# Sheet1.net
KiCad netlist of a schematic drawn in Altium Designer
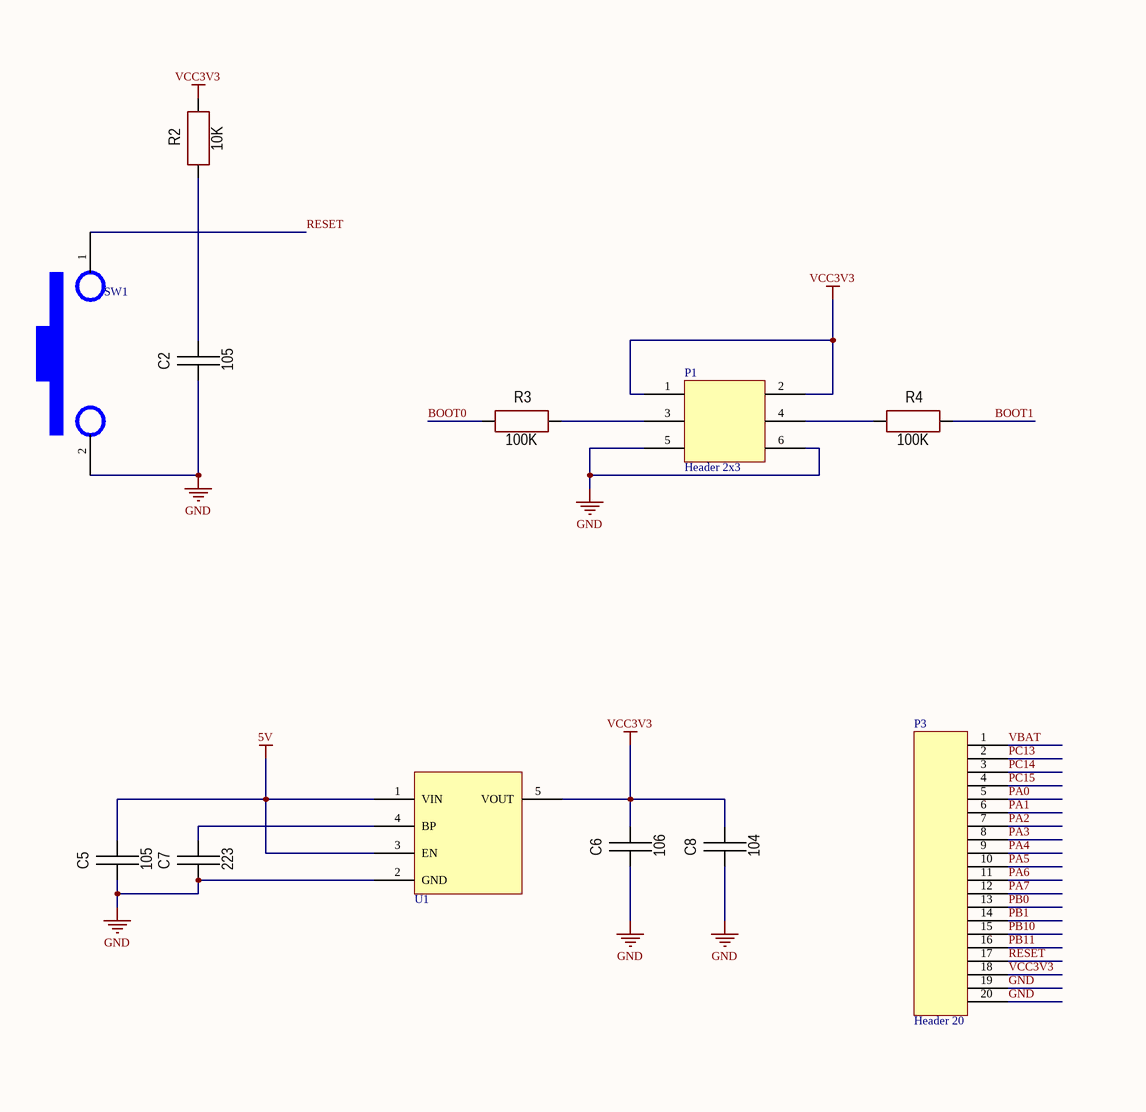
[diagram p0: Sheet1.SchDoc, top left]
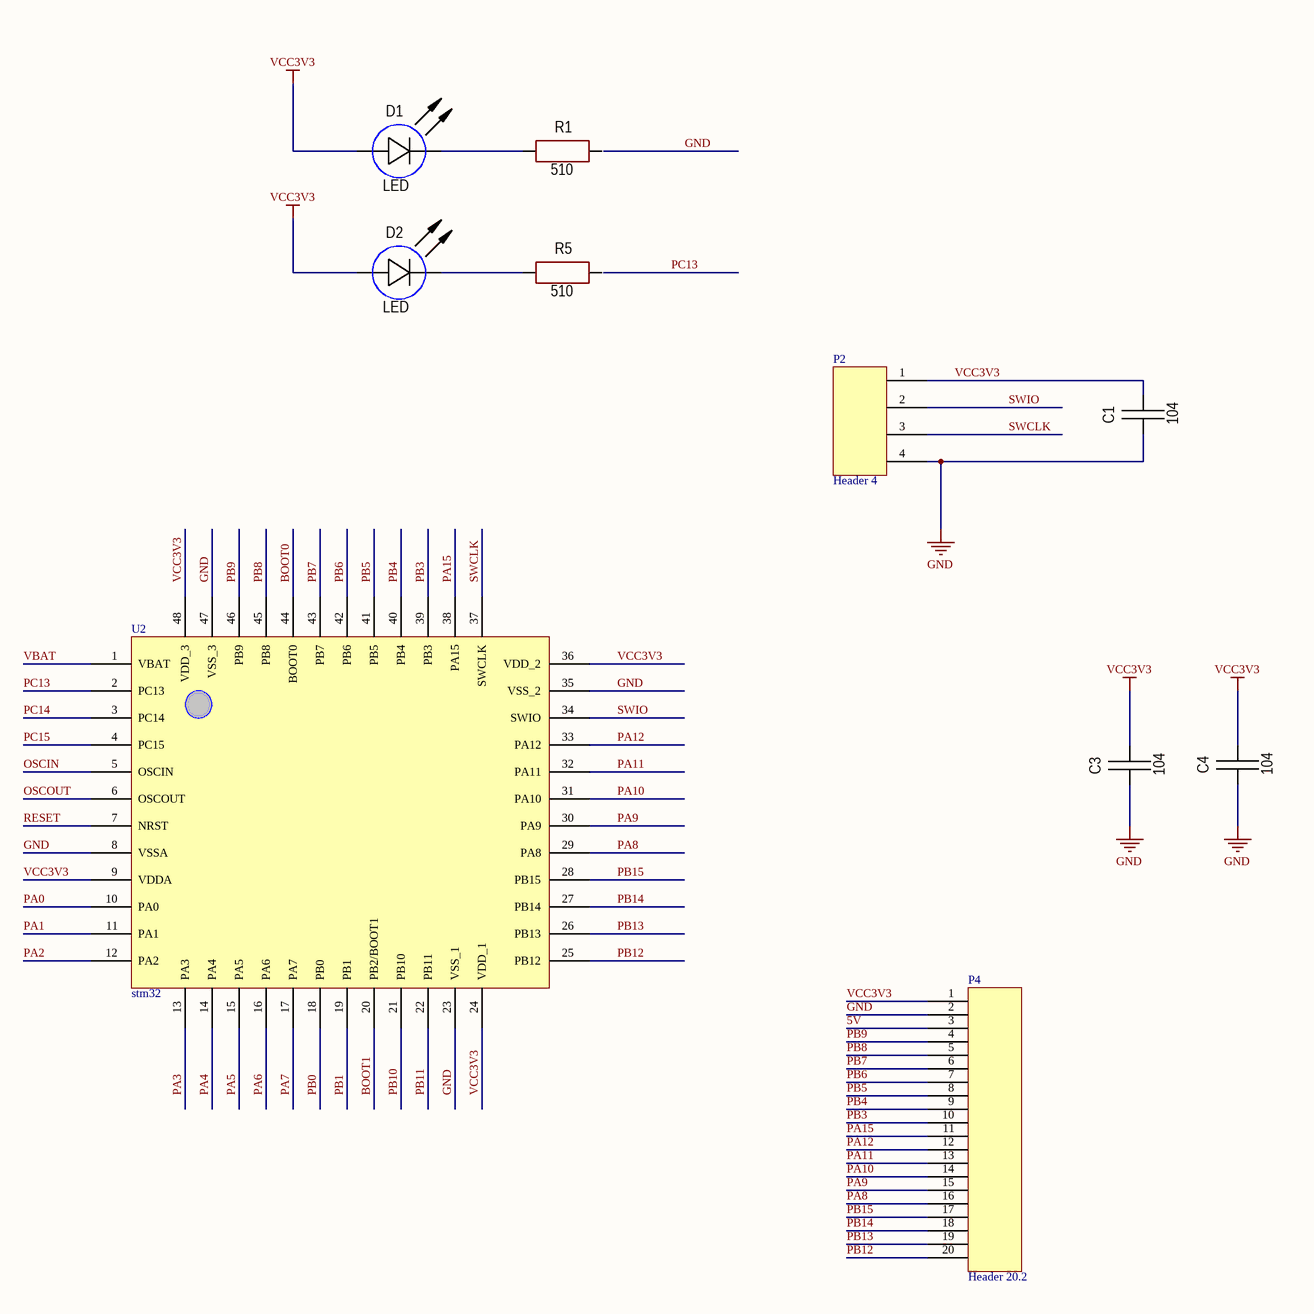
[diagram p1: Sheet1.SchDoc, top right]
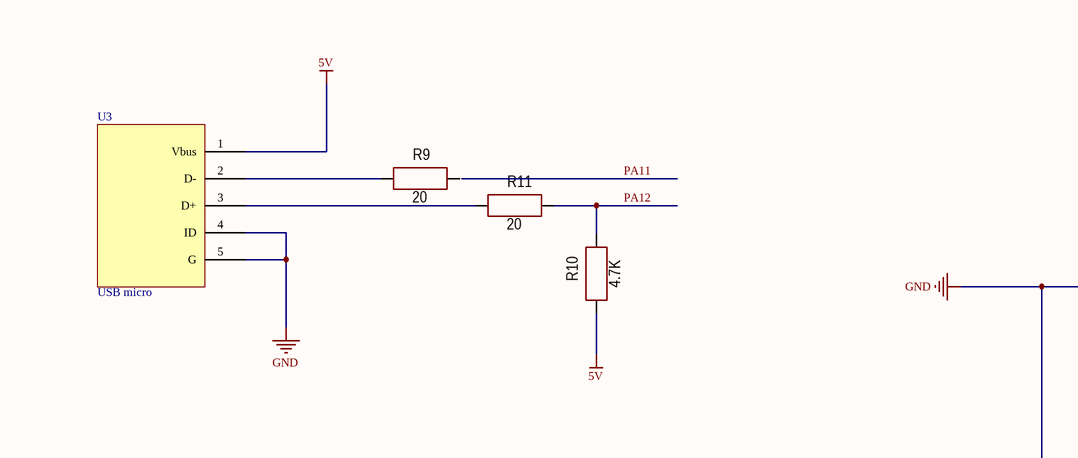
[diagram p2: Sheet1.SchDoc, bottom left]
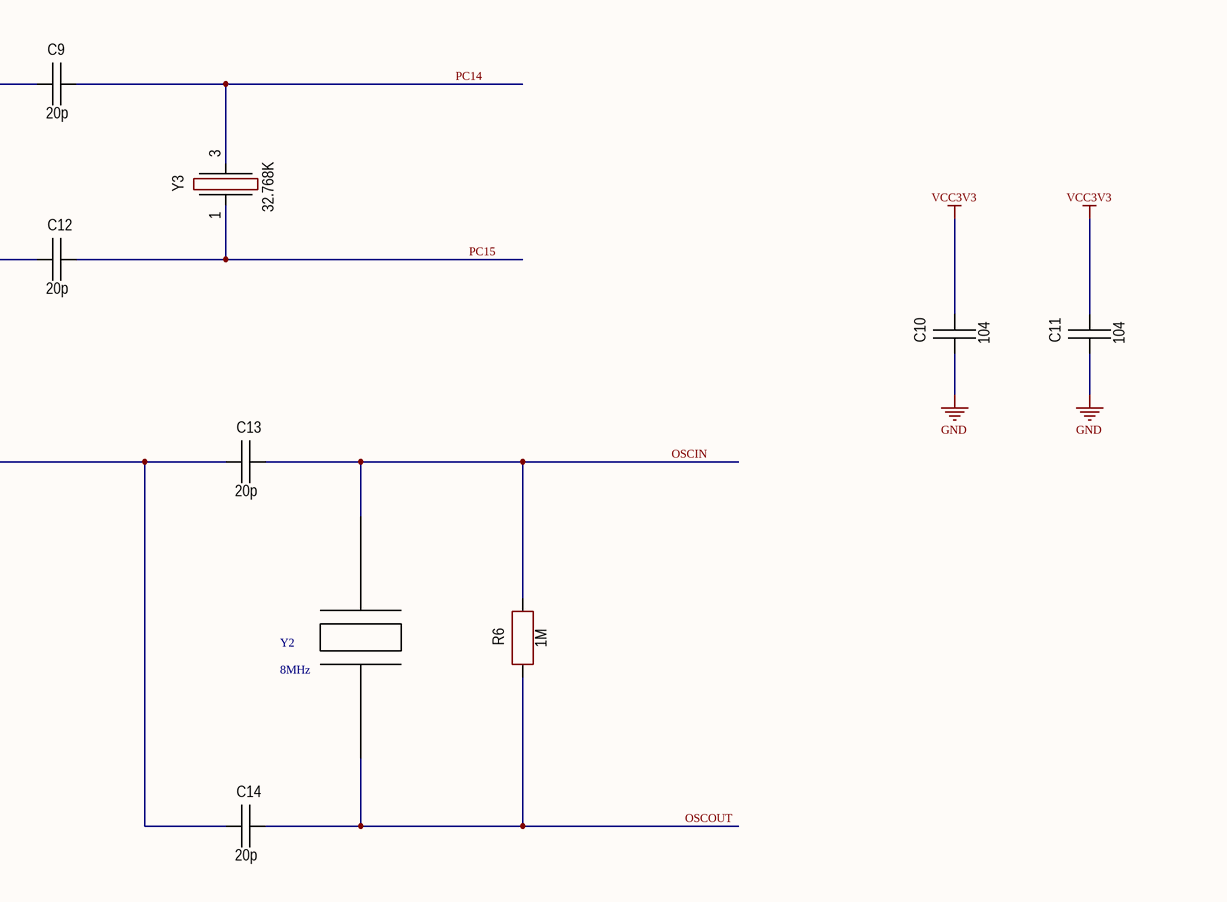
[diagram p3: Sheet1.SchDoc, bottom right]

(export (version "E")
  (design (tool "Eeschema 10.0.6"))
  (components
    (comp (ref "C1") (value "104") (footprint "CH0603C") (libsource (lib "Discrete") (part "Capacitor")))
    (comp (ref "C2") (value "105") (footprint "CH0603C") (libsource (lib "Discrete") (part "Capacitor")))
    (comp (ref "C3") (value "104") (footprint "CH0603C") (libsource (lib "Discrete") (part "Capacitor")))
    (comp (ref "C4") (value "104") (footprint "CH0603C") (libsource (lib "Discrete") (part "Capacitor")))
    (comp (ref "C5") (value "105") (footprint "CH0603C") (libsource (lib "Discrete") (part "Capacitor")))
    (comp (ref "C6") (value "106") (footprint "CH0603C") (libsource (lib "Discrete") (part "Capacitor")))
    (comp (ref "C7") (value "223") (footprint "CH0603C") (libsource (lib "Discrete") (part "Capacitor")))
    (comp (ref "C8") (value "104") (footprint "CH0603C") (libsource (lib "Discrete") (part "Capacitor")))
    (comp (ref "C9") (value "20p") (footprint "CH0603C") (libsource (lib "Discrete") (part "Capacitor")))
    (comp (ref "C10") (value "104") (footprint "CH0603C") (libsource (lib "Discrete") (part "Capacitor")))
    (comp (ref "C11") (value "104") (footprint "CH0603C") (libsource (lib "Discrete") (part "Capacitor")))
    (comp (ref "C12") (value "20p") (footprint "CH0603C") (libsource (lib "Discrete") (part "Capacitor")))
    (comp (ref "C13") (value "20p") (footprint "CH0603C") (libsource (lib "Discrete") (part "Capacitor")))
    (comp (ref "C14") (value "20p") (footprint "CH0603C") (libsource (lib "Discrete") (part "Capacitor")))
    (comp (ref "D1") (value "LED") (footprint "CH0603LB") (libsource (lib "Discrete") (part "LED")))
    (comp (ref "D2") (value "LED") (footprint "CH0603LR") (libsource (lib "Discrete") (part "LED")))
    (comp (ref "P1")
      (value "Header 2x3")
      (footprint "Header 3X2")
      (libsource (lib "Library") (part "Header 2x3"))
    )
    (comp (ref "P2") (value "Header 4") (footprint "header 4") (libsource (lib "Library") (part "Header 4")))
    (comp (ref "P3") (value "Header 20") (footprint "Header 20") (libsource (lib "") (part "Header 20_1")))
    (comp (ref "P4")
      (value "Header 20.2")
      (footprint "Header 20")
      (libsource (lib "Library") (part "Header 20"))
    )
    (comp (ref "R1") (value "510") (footprint "CH0603R") (libsource (lib "Discrete") (part "Resistor")))
    (comp (ref "R2") (value "10K") (footprint "CH0603R") (libsource (lib "") (part "Resistor_1")))
    (comp (ref "R3") (value "100K") (footprint "CH0603R") (libsource (lib "Discrete") (part "Resistor")))
    (comp (ref "R4") (value "100K") (footprint "CH0603R") (libsource (lib "Discrete") (part "Resistor")))
    (comp (ref "R5") (value "510") (footprint "CH0603R") (libsource (lib "Discrete") (part "Resistor")))
    (comp (ref "R6") (value "1M") (footprint "CH0603R") (libsource (lib "") (part "Resistor_1")))
    (comp (ref "R9") (value "20") (footprint "CH0603R") (libsource (lib "Discrete") (part "Resistor")))
    (comp (ref "R10") (value "4.7K") (footprint "CH0603R") (libsource (lib "") (part "Resistor_1")))
    (comp (ref "R11") (value "20") (footprint "CH0603R") (libsource (lib "Discrete") (part "Resistor")))
    (comp (ref "SW1") (value "Switch") (footprint "Switch") (libsource (lib "Library") (part "Switch")))
    (comp (ref "U1")
      (value "Regulator")
      (footprint "MIC5205-3.3YM5-TR")
      (libsource (lib "Library") (part "Regulator"))
    )
    (comp (ref "U2") (value "stm32") (footprint "STM32F103C8T6") (libsource (lib "Library") (part "stm32")))
    (comp (ref "U3")
      (value "USB micro")
      (footprint "USB MICRO")
      (libsource (lib "Library") (part "USB micro"))
    )
    (comp (ref "Y2") (value "8MHz") (footprint "HC49") (libsource (lib "Library") (part "Oscillator")))
    (comp (ref "Y3")
      (value "32.768K")
      (footprint "OSC: 3215")
      (libsource (lib "Discrete") (part "Oscillator"))
    )
  )
  (nets
    (net (code "1") (name "/BOOT0") (class "Default")
      (node (ref "R3") (pin "1") (pinfunction "1_1") (pintype "passive"))
      (node (ref "U2") (pin "44") (pinfunction "BOOT0_44") (pintype "passive"))
    )
    (net (code "2") (name "/BOOT1") (class "Default")
      (node (ref "R4") (pin "2") (pinfunction "2_2") (pintype "passive"))
      (node (ref "U2") (pin "20") (pinfunction "PB2/BOOT1_20") (pintype "passive"))
    )
    (net (code "3") (name "/OSCIN") (class "Default")
      (node (ref "R6") (pin "2") (pinfunction "2_2") (pintype "passive"))
      (node (ref "U2") (pin "5") (pinfunction "OSCIN_5") (pintype "passive"))
      (node (ref "Y2") (pin "2") (pinfunction "2_2") (pintype "passive"))
    )
    (net (code "4") (name "/OSCOUT") (class "Default")
      (node (ref "C14") (pin "2") (pinfunction "2_2") (pintype "power_in"))
      (node (ref "R6") (pin "1") (pinfunction "1_1") (pintype "passive"))
      (node (ref "U2") (pin "6") (pinfunction "OSCOUT_6") (pintype "passive"))
      (node (ref "Y2") (pin "1") (pinfunction "1_1") (pintype "passive"))
    )
    (net (code "5") (name "/PA0") (class "Default")
      (node (ref "P3") (pin "5") (pinfunction "5_5") (pintype "passive"))
      (node (ref "U2") (pin "10") (pinfunction "PA0_10") (pintype "passive"))
    )
    (net (code "6") (name "/PA1") (class "Default")
      (node (ref "P3") (pin "6") (pinfunction "6_6") (pintype "passive"))
      (node (ref "U2") (pin "11") (pinfunction "PA1_11") (pintype "passive"))
    )
    (net (code "7") (name "/PA2") (class "Default")
      (node (ref "P3") (pin "7") (pinfunction "7_7") (pintype "passive"))
      (node (ref "U2") (pin "12") (pinfunction "PA2_12") (pintype "passive"))
    )
    (net (code "8") (name "/PA3") (class "Default")
      (node (ref "P3") (pin "8") (pinfunction "8_8") (pintype "passive"))
      (node (ref "U2") (pin "13") (pinfunction "PA3_13") (pintype "passive"))
    )
    (net (code "9") (name "/PA4") (class "Default")
      (node (ref "P3") (pin "9") (pinfunction "9_9") (pintype "passive"))
      (node (ref "U2") (pin "14") (pinfunction "PA4_14") (pintype "passive"))
    )
    (net (code "10") (name "/PA5") (class "Default")
      (node (ref "P3") (pin "10") (pinfunction "10_10") (pintype "passive"))
      (node (ref "U2") (pin "15") (pinfunction "PA5_15") (pintype "passive"))
    )
    (net (code "11") (name "/PA6") (class "Default")
      (node (ref "P3") (pin "11") (pinfunction "11_11") (pintype "passive"))
      (node (ref "U2") (pin "16") (pinfunction "PA6_16") (pintype "passive"))
    )
    (net (code "12") (name "/PA7") (class "Default")
      (node (ref "P3") (pin "12") (pinfunction "12_12") (pintype "passive"))
      (node (ref "U2") (pin "17") (pinfunction "PA7_17") (pintype "passive"))
    )
    (net (code "13") (name "/PA8") (class "Default")
      (node (ref "P4") (pin "16") (pinfunction "16_16") (pintype "passive"))
      (node (ref "U2") (pin "29") (pinfunction "PA8_29") (pintype "passive"))
    )
    (net (code "14") (name "/PA9") (class "Default")
      (node (ref "P4") (pin "15") (pinfunction "15_15") (pintype "passive"))
      (node (ref "U2") (pin "30") (pinfunction "PA9_30") (pintype "passive"))
    )
    (net (code "15") (name "/PA10") (class "Default")
      (node (ref "P4") (pin "14") (pinfunction "14_14") (pintype "passive"))
      (node (ref "U2") (pin "31") (pinfunction "PA10_31") (pintype "passive"))
    )
    (net (code "16") (name "/PA11") (class "Default")
      (node (ref "P4") (pin "13") (pinfunction "13_13") (pintype "passive"))
      (node (ref "U2") (pin "32") (pinfunction "PA11_32") (pintype "passive"))
    )
    (net (code "17") (name "/PA12") (class "Default")
      (node (ref "P4") (pin "12") (pinfunction "12_12") (pintype "passive"))
      (node (ref "R10") (pin "2") (pinfunction "2_2") (pintype "passive"))
      (node (ref "R11") (pin "2") (pinfunction "2_2") (pintype "passive"))
      (node (ref "U2") (pin "33") (pinfunction "PA12_33") (pintype "passive"))
    )
    (net (code "18") (name "/PA15") (class "Default")
      (node (ref "P4") (pin "11") (pinfunction "11_11") (pintype "passive"))
      (node (ref "U2") (pin "38") (pinfunction "PA15_38") (pintype "passive"))
    )
    (net (code "19") (name "/PB0") (class "Default")
      (node (ref "P3") (pin "13") (pinfunction "13_13") (pintype "passive"))
      (node (ref "U2") (pin "18") (pinfunction "PB0_18") (pintype "passive"))
    )
    (net (code "20") (name "/PB1") (class "Default")
      (node (ref "P3") (pin "14") (pinfunction "14_14") (pintype "passive"))
      (node (ref "U2") (pin "19") (pinfunction "PB1_19") (pintype "passive"))
    )
    (net (code "21") (name "/PB3") (class "Default")
      (node (ref "P4") (pin "10") (pinfunction "10_10") (pintype "passive"))
      (node (ref "U2") (pin "39") (pinfunction "PB3_39") (pintype "passive"))
    )
    (net (code "22") (name "/PB4") (class "Default")
      (node (ref "P4") (pin "9") (pinfunction "9_9") (pintype "passive"))
      (node (ref "U2") (pin "40") (pinfunction "PB4_40") (pintype "passive"))
    )
    (net (code "23") (name "/PB5") (class "Default")
      (node (ref "P4") (pin "8") (pinfunction "8_8") (pintype "passive"))
      (node (ref "U2") (pin "41") (pinfunction "PB5_41") (pintype "passive"))
    )
    (net (code "24") (name "/PB6") (class "Default")
      (node (ref "P4") (pin "7") (pinfunction "7_7") (pintype "passive"))
      (node (ref "U2") (pin "42") (pinfunction "PB6_42") (pintype "passive"))
    )
    (net (code "25") (name "/PB7") (class "Default")
      (node (ref "P4") (pin "6") (pinfunction "6_6") (pintype "passive"))
      (node (ref "U2") (pin "43") (pinfunction "PB7_43") (pintype "passive"))
    )
    (net (code "26") (name "/PB8") (class "Default")
      (node (ref "P4") (pin "5") (pinfunction "5_5") (pintype "passive"))
      (node (ref "U2") (pin "45") (pinfunction "PB8_45") (pintype "passive"))
    )
    (net (code "27") (name "/PB9") (class "Default")
      (node (ref "P4") (pin "4") (pinfunction "4_4") (pintype "passive"))
      (node (ref "U2") (pin "46") (pinfunction "PB9_46") (pintype "passive"))
    )
    (net (code "28") (name "/PB10") (class "Default")
      (node (ref "P3") (pin "15") (pinfunction "15_15") (pintype "passive"))
      (node (ref "U2") (pin "21") (pinfunction "PB10_21") (pintype "passive"))
    )
    (net (code "29") (name "/PB11") (class "Default")
      (node (ref "P3") (pin "16") (pinfunction "16_16") (pintype "passive"))
      (node (ref "U2") (pin "22") (pinfunction "PB11_22") (pintype "passive"))
    )
    (net (code "30") (name "/PB12") (class "Default")
      (node (ref "P4") (pin "20") (pinfunction "20_20") (pintype "passive"))
      (node (ref "U2") (pin "25") (pinfunction "PB12_25") (pintype "passive"))
    )
    (net (code "31") (name "/PB13") (class "Default")
      (node (ref "P4") (pin "19") (pinfunction "19_19") (pintype "passive"))
      (node (ref "U2") (pin "26") (pinfunction "PB13_26") (pintype "passive"))
    )
    (net (code "32") (name "/PB14") (class "Default")
      (node (ref "P4") (pin "18") (pinfunction "18_18") (pintype "passive"))
      (node (ref "U2") (pin "27") (pinfunction "PB14_27") (pintype "passive"))
    )
    (net (code "33") (name "/PB15") (class "Default")
      (node (ref "P4") (pin "17") (pinfunction "17_17") (pintype "passive"))
      (node (ref "U2") (pin "28") (pinfunction "PB15_28") (pintype "passive"))
    )
    (net (code "34") (name "/PC13") (class "Default")
      (node (ref "P3") (pin "2") (pinfunction "2_2") (pintype "passive"))
      (node (ref "U2") (pin "2") (pinfunction "PC13_2") (pintype "passive"))
    )
    (net (code "35") (name "/PC14") (class "Default")
      (node (ref "C9") (pin "2") (pinfunction "2_2") (pintype "power_in"))
      (node (ref "P3") (pin "3") (pinfunction "3_3") (pintype "passive"))
      (node (ref "U2") (pin "3") (pinfunction "PC14_3") (pintype "passive"))
      (node (ref "Y3") (pin "3") (pinfunction "3_3") (pintype "passive"))
    )
    (net (code "36") (name "/PC15") (class "Default")
      (node (ref "C12") (pin "2") (pinfunction "2_2") (pintype "power_in"))
      (node (ref "P3") (pin "4") (pinfunction "4_4") (pintype "passive"))
      (node (ref "U2") (pin "4") (pinfunction "PC15_4") (pintype "passive"))
      (node (ref "Y3") (pin "1") (pinfunction "1_1") (pintype "passive"))
    )
    (net (code "37") (name "/RESET") (class "Default")
      (node (ref "P3") (pin "17") (pinfunction "17_17") (pintype "passive"))
      (node (ref "SW1") (pin "1") (pinfunction "1_1") (pintype "passive"))
      (node (ref "U2") (pin "7") (pinfunction "NRST_7") (pintype "passive"))
    )
    (net (code "38") (name "/SWCLK") (class "Default")
      (node (ref "P2") (pin "3") (pinfunction "3_3") (pintype "passive"))
      (node (ref "U2") (pin "37") (pinfunction "SWCLK_37") (pintype "passive"))
    )
    (net (code "39") (name "/SWIO") (class "Default")
      (node (ref "P2") (pin "2") (pinfunction "2_2") (pintype "passive"))
      (node (ref "U2") (pin "34") (pinfunction "SWIO_34") (pintype "passive"))
    )
    (net (code "40") (name "/VBAT") (class "Default")
      (node (ref "P3") (pin "1") (pinfunction "1_1") (pintype "passive"))
      (node (ref "U2") (pin "1") (pinfunction "VBAT_1") (pintype "passive"))
    )
    (net (code "41") (name "5V") (class "Default")
      (node (ref "C5") (pin "2") (pinfunction "2_2") (pintype "power_in"))
      (node (ref "P4") (pin "3") (pinfunction "3_3") (pintype "passive"))
      (node (ref "R10") (pin "1") (pinfunction "1_1") (pintype "passive"))
      (node (ref "U1") (pin "1") (pinfunction "VIN_1") (pintype "passive"))
      (node (ref "U1") (pin "3") (pinfunction "EN_3") (pintype "passive"))
      (node (ref "U3") (pin "1") (pinfunction "Vbus_1") (pintype "passive"))
    )
    (net (code "42") (name "GND") (class "Default")
      (node (ref "C1") (pin "1") (pinfunction "1_1") (pintype "power_in"))
      (node (ref "C10") (pin "1") (pinfunction "1_1") (pintype "power_in"))
      (node (ref "C11") (pin "1") (pinfunction "1_1") (pintype "power_in"))
      (node (ref "C12") (pin "1") (pinfunction "1_1") (pintype "power_in"))
      (node (ref "C13") (pin "1") (pinfunction "1_1") (pintype "power_in"))
      (node (ref "C14") (pin "1") (pinfunction "1_1") (pintype "power_in"))
      (node (ref "C2") (pin "1") (pinfunction "1_1") (pintype "power_in"))
      (node (ref "C3") (pin "1") (pinfunction "1_1") (pintype "power_in"))
      (node (ref "C4") (pin "1") (pinfunction "1_1") (pintype "power_in"))
      (node (ref "C5") (pin "1") (pinfunction "1_1") (pintype "power_in"))
      (node (ref "C6") (pin "1") (pinfunction "1_1") (pintype "power_in"))
      (node (ref "C7") (pin "1") (pinfunction "1_1") (pintype "power_in"))
      (node (ref "C8") (pin "1") (pinfunction "1_1") (pintype "power_in"))
      (node (ref "C9") (pin "1") (pinfunction "1_1") (pintype "power_in"))
      (node (ref "P1") (pin "5") (pinfunction "5_5") (pintype "passive"))
      (node (ref "P1") (pin "6") (pinfunction "6_6") (pintype "passive"))
      (node (ref "P2") (pin "4") (pinfunction "4_4") (pintype "passive"))
      (node (ref "P3") (pin "19") (pinfunction "19_19") (pintype "passive"))
      (node (ref "P3") (pin "20") (pinfunction "20_20") (pintype "passive"))
      (node (ref "P4") (pin "2") (pinfunction "2_2") (pintype "passive"))
      (node (ref "SW1") (pin "2") (pinfunction "2_2") (pintype "passive"))
      (node (ref "U1") (pin "2") (pinfunction "GND_2") (pintype "passive"))
      (node (ref "U2") (pin "23") (pinfunction "VSS_1_23") (pintype "passive"))
      (node (ref "U2") (pin "35") (pinfunction "VSS_2_35") (pintype "passive"))
      (node (ref "U2") (pin "47") (pinfunction "VSS_3_47") (pintype "passive"))
      (node (ref "U2") (pin "8") (pinfunction "VSSA_8") (pintype "passive"))
      (node (ref "U3") (pin "4") (pinfunction "ID_4") (pintype "passive"))
      (node (ref "U3") (pin "5") (pinfunction "G_5") (pintype "passive"))
    )
    (net (code "43") (name "Net-(C2-Pad2)") (class "Default")
      (node (ref "C2") (pin "2") (pinfunction "2_2") (pintype "power_in"))
      (node (ref "R2") (pin "1") (pinfunction "1_1") (pintype "passive"))
    )
    (net (code "44") (name "Net-(D1-C)") (class "Default")
      (node (ref "D1") (pin "2") (pinfunction "C_2") (pintype "passive"))
      (node (ref "R1") (pin "1") (pinfunction "1_1") (pintype "passive"))
    )
    (net (code "45") (name "Net-(D2-C)") (class "Default")
      (node (ref "D2") (pin "2") (pinfunction "C_2") (pintype "passive"))
      (node (ref "R5") (pin "1") (pinfunction "1_1") (pintype "passive"))
    )
    (net (code "46") (name "Net-(P1-Pad3)") (class "Default")
      (node (ref "P1") (pin "3") (pinfunction "3_3") (pintype "passive"))
      (node (ref "R3") (pin "2") (pinfunction "2_2") (pintype "passive"))
    )
    (net (code "47") (name "Net-(P1-Pad4)") (class "Default")
      (node (ref "P1") (pin "4") (pinfunction "4_4") (pintype "passive"))
      (node (ref "R4") (pin "1") (pinfunction "1_1") (pintype "passive"))
    )
    (net (code "48") (name "Net-(U1-BP)") (class "Default")
      (node (ref "C7") (pin "2") (pinfunction "2_2") (pintype "power_in"))
      (node (ref "U1") (pin "4") (pinfunction "BP_4") (pintype "passive"))
    )
    (net (code "49") (name "Net-(U3-D+)") (class "Default")
      (node (ref "R11") (pin "1") (pinfunction "1_1") (pintype "passive"))
      (node (ref "U3") (pin "3") (pinfunction "D+_3") (pintype "passive"))
    )
    (net (code "50") (name "Net-(U3-D-)") (class "Default")
      (node (ref "R9") (pin "1") (pinfunction "1_1") (pintype "passive"))
      (node (ref "U3") (pin "2") (pinfunction "D-_2") (pintype "passive"))
    )
    (net (code "51") (name "VCC3V3") (class "Default")
      (node (ref "C1") (pin "2") (pinfunction "2_2") (pintype "power_in"))
      (node (ref "C11") (pin "2") (pinfunction "2_2") (pintype "power_in"))
      (node (ref "C3") (pin "2") (pinfunction "2_2") (pintype "power_in"))
      (node (ref "C4") (pin "2") (pinfunction "2_2") (pintype "power_in"))
      (node (ref "C8") (pin "2") (pinfunction "2_2") (pintype "power_in"))
      (node (ref "D1") (pin "1") (pinfunction "A_1") (pintype "passive"))
      (node (ref "D2") (pin "1") (pinfunction "A_1") (pintype "passive"))
      (node (ref "P1") (pin "1") (pinfunction "1_1") (pintype "passive"))
      (node (ref "P1") (pin "2") (pinfunction "2_2") (pintype "passive"))
      (node (ref "P2") (pin "1") (pinfunction "1_1") (pintype "passive"))
      (node (ref "P3") (pin "18") (pinfunction "18_18") (pintype "passive"))
      (node (ref "P4") (pin "1") (pinfunction "1_1") (pintype "passive"))
      (node (ref "R2") (pin "2") (pinfunction "2_2") (pintype "passive"))
      (node (ref "U1") (pin "5") (pinfunction "VOUT_5") (pintype "passive"))
      (node (ref "U2") (pin "24") (pinfunction "VDD_1_24") (pintype "passive"))
      (node (ref "U2") (pin "36") (pinfunction "VDD_2_36") (pintype "passive"))
      (node (ref "U2") (pin "48") (pinfunction "VDD_3_48") (pintype "passive"))
      (node (ref "U2") (pin "9") (pinfunction "VDDA_9") (pintype "passive"))
    )
    (net (code "52") (name "unconnected-(C6-Pad2)") (class "Default")
      (node (ref "C6") (pin "2") (pinfunction "2_2") (pintype "power_in"))
    )
    (net (code "53") (name "unconnected-(C10-Pad2)") (class "Default")
      (node (ref "C10") (pin "2") (pinfunction "2_2") (pintype "power_in"))
    )
    (net (code "54") (name "unconnected-(C13-Pad2)") (class "Default")
      (node (ref "C13") (pin "2") (pinfunction "2_2") (pintype "power_in"))
    )
    (net (code "55") (name "unconnected-(R1-Pad2)") (class "Default")
      (node (ref "R1") (pin "2") (pinfunction "2_2") (pintype "passive"))
    )
    (net (code "56") (name "unconnected-(R5-Pad2)") (class "Default")
      (node (ref "R5") (pin "2") (pinfunction "2_2") (pintype "passive"))
    )
    (net (code "57") (name "unconnected-(R9-Pad2)") (class "Default")
      (node (ref "R9") (pin "2") (pinfunction "2_2") (pintype "passive"))
    )
  )
)
